# SCH_Arduino-Nano_2025-06-12.net
KiCad netlist of a schematic drawn in EasyEDA
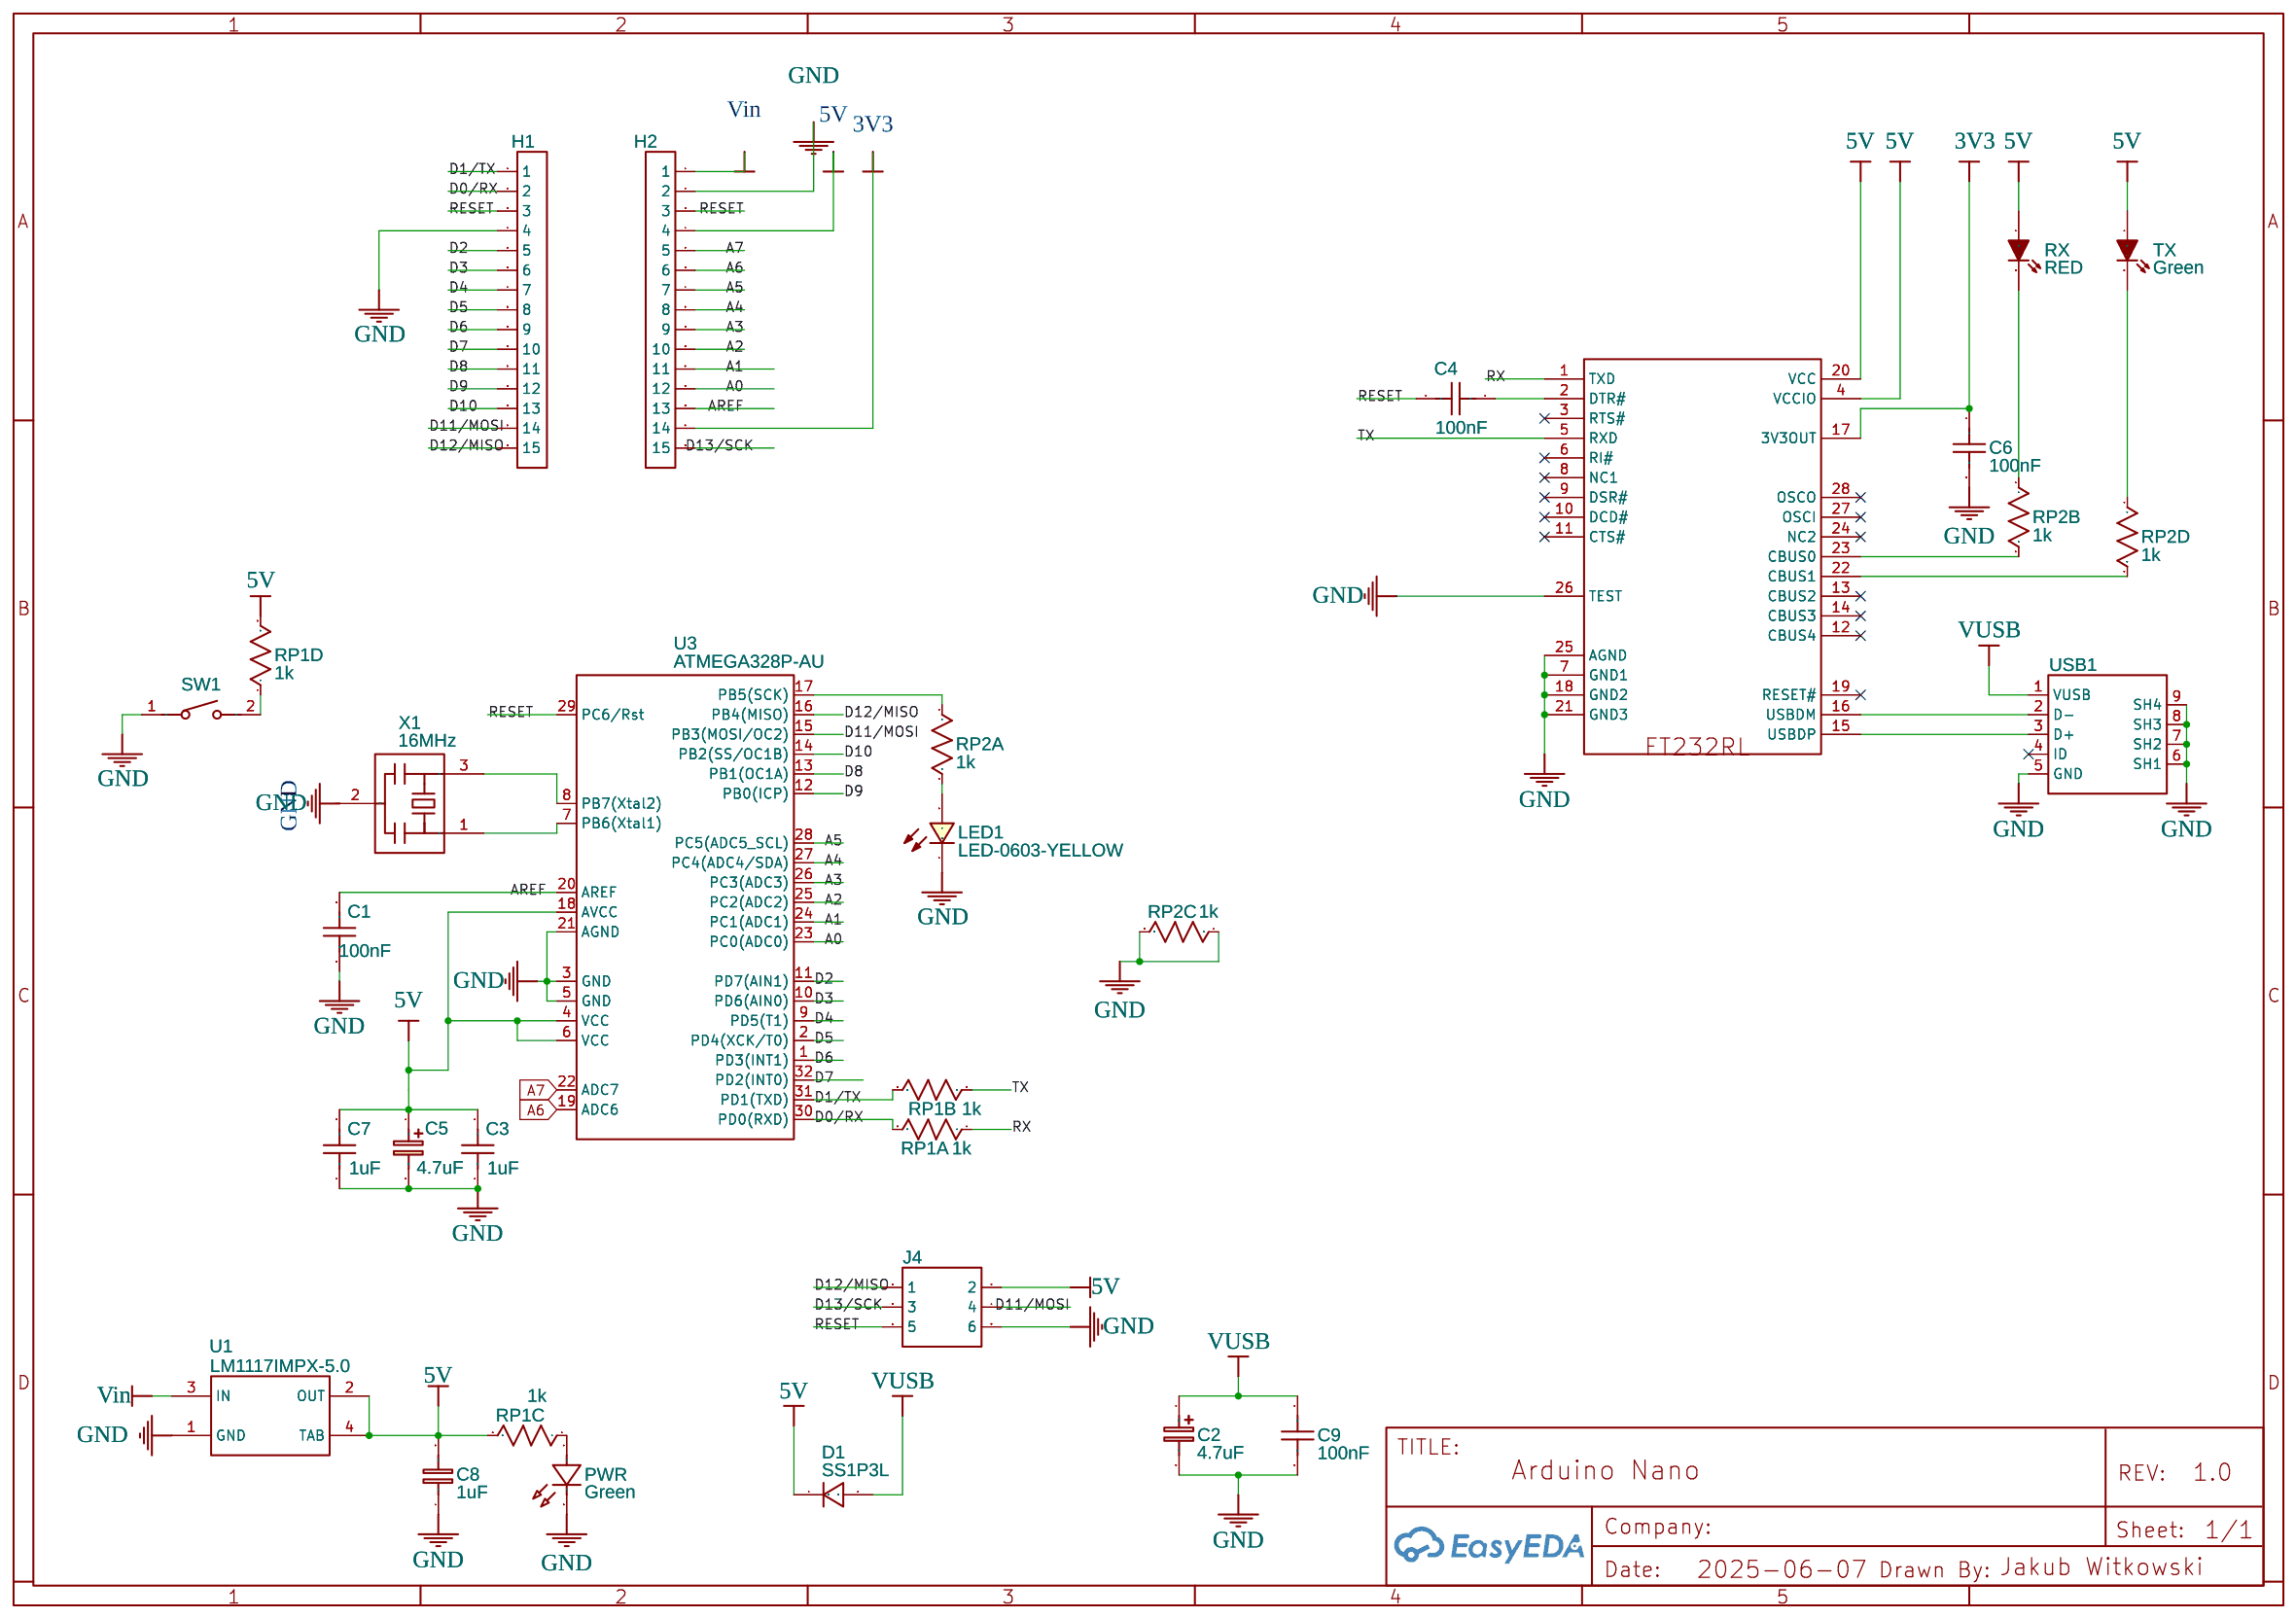
[diagram p0: schematic sheet]

(export (version "E")
  (design (tool "Eeschema 10.0.6"))
  (components
    (comp (ref "C1") (value "100nF") (libsource (lib "") (part "C_0603_US_1")))
    (comp (ref "C2") (value "4.7uF") (libsource (lib "") (part "C_Tan_SMD_A_EU_1")))
    (comp (ref "C3") (value "1uF") (libsource (lib "") (part "C_0603_US_1")))
    (comp (ref "C4") (value "100nF") (libsource (lib "") (part "C_0603_US")))
    (comp (ref "C5") (value "4.7uF") (libsource (lib "") (part "C_Tan_SMD_A_EU")))
    (comp (ref "C6") (value "100nF") (libsource (lib "") (part "C_0603_US_2")))
    (comp (ref "C7") (value "1uF") (libsource (lib "") (part "C_0603_US_1")))
    (comp (ref "C8") (value "1uF") (libsource (lib "") (part "C_0603_EU")))
    (comp (ref "C9") (value "100nF") (libsource (lib "") (part "C_0603_US_2")))
    (comp (ref "D1")
      (value "SS1P3L")
      (fields (field (name "Manufacturer Part") "1N4148W") (field (name "Manufacturer") "Tak Cheong"))
      (libsource (lib "") (part "1N4148W"))
    )
    (comp (ref "H1")
      (value "Header-Female-2.54_1x15")
      (fields
        (field (name "Manufacturer Part") "220S-1*15P H=8.5MM Ytype Gold-plated")
        (field (name "Manufacturer") "Ckmtw")
      )
      (libsource (lib "") (part "Header-Female-2.54_1x15_1"))
    )
    (comp (ref "H2")
      (value "Header-Female-2.54_1x15")
      (fields
        (field (name "Manufacturer Part") "220S-1*15P H=8.5MM Ytype Gold-plated")
        (field (name "Manufacturer") "Ckmtw")
      )
      (libsource (lib "") (part "Header-Female-2.54_1x15"))
    )
    (comp (ref "J4") (value "HDR-M-2.54_2x3") (libsource (lib "") (part "HDR-M-2.54_2x3")))
    (comp (ref "LED1")
      (value "LED-0603-YELLOW")
      (fields
        (field (name "Manufacturer Part") "19-213/Y2C-CQ1R1L/3T")
        (field (name "Manufacturer") "Everlight Elec")
      )
      (libsource (lib "") (part "LED-0603-YELLOW"))
    )
    (comp (ref "PWR")
      (value "Green")
      (fields (field (name "Manufacturer Part") "GreenLED"))
      (libsource (lib "") (part "GREENLED_C9900016840"))
    )
    (comp (ref "RP1A") (value "1k") (libsource (lib "") (part "R_0603_US_4")))
    (comp (ref "RP1B") (value "1k") (libsource (lib "") (part "R_0603_US_3")))
    (comp (ref "RP1C") (value "1k") (libsource (lib "") (part "R_0603_US_5")))
    (comp (ref "RP1D") (value "1k") (libsource (lib "") (part "R_0603_US")))
    (comp (ref "RP2A") (value "1k") (libsource (lib "") (part "R_0603_US_7")))
    (comp (ref "RP2B") (value "1k") (libsource (lib "") (part "R_0603_US_6")))
    (comp (ref "RP2C") (value "1k") (libsource (lib "") (part "R_0603_US_1")))
    (comp (ref "RP2D") (value "1k") (libsource (lib "") (part "R_0603_US_2")))
    (comp (ref "RX")
      (value "RED")
      (fields (field (name "Manufacturer Part") "KT-0603R") (field (name "Manufacturer") "Hubei KENTO Elec"))
      (libsource (lib "") (part "LED-0603-RED"))
    )
    (comp (ref "SW1")
      (value "TS-1088-AR02016")
      (fields (field (name "Manufacturer") "XUNPU"))
      (libsource (lib "") (part "TS-1088-AR02016"))
    )
    (comp (ref "TX")
      (value "Green")
      (fields
        (field (name "Manufacturer Part") "SZYY0603YG")
        (field (name "Manufacturer") "Yongyu Photoelectric")
      )
      (libsource (lib "") (part "LED-0603-GREEN"))
    )
    (comp (ref "U1")
      (value "LM1117IMPX-5.0")
      (fields (field (name "Manufacturer") "TI(德州仪器)"))
      (libsource (lib "") (part "LM1117IMPX-5.0"))
    )
    (comp (ref "U2")
      (value "FT232RL")
      (fields (field (name "Manufacturer Part") "?"))
      (libsource (lib "") (part "Unknown_795_-630"))
    )
    (comp (ref "U3")
      (value "ATMEGA328P-AU")
      (fields (field (name "Manufacturer") "Microchip Technology / Atmel"))
      (libsource (lib "") (part "ATMEGA328P-AU"))
    )
    (comp (ref "USB1") (value "USB_MINI") (libsource (lib "") (part "USB_MINI")))
    (comp (ref "X1")
      (value "16MHz")
      (fields (field (name "Manufacturer Part") "CSTCE16M0V53-R0") (field (name "Manufacturer") "MuRata"))
      (libsource (lib "") (part "CSTCE16M0V53C-R0"))
    )
  )
  (nets
    (net (code "1") (name "/A0") (class "Default")
      (node (ref "H2") (pin "12") (pinfunction "12_12") (pintype "unspecified"))
      (node (ref "U3") (pin "23") (pinfunction "PC0(ADC0)_23") (pintype "unspecified"))
    )
    (net (code "2") (name "/A1") (class "Default")
      (node (ref "H2") (pin "11") (pinfunction "11_11") (pintype "unspecified"))
      (node (ref "U3") (pin "24") (pinfunction "PC1(ADC1)_24") (pintype "unspecified"))
    )
    (net (code "3") (name "/A2") (class "Default")
      (node (ref "H2") (pin "10") (pinfunction "10_10") (pintype "unspecified"))
      (node (ref "U3") (pin "25") (pinfunction "PC2(ADC2)_25") (pintype "unspecified"))
    )
    (net (code "4") (name "/A3") (class "Default")
      (node (ref "H2") (pin "9") (pinfunction "9_9") (pintype "unspecified"))
      (node (ref "U3") (pin "26") (pinfunction "PC3(ADC3)_26") (pintype "unspecified"))
    )
    (net (code "5") (name "/A4") (class "Default")
      (node (ref "H2") (pin "8") (pinfunction "8_8") (pintype "unspecified"))
      (node (ref "U3") (pin "27") (pinfunction "PC4(ADC4/SDA)_27") (pintype "unspecified"))
    )
    (net (code "6") (name "/A5") (class "Default")
      (node (ref "H2") (pin "7") (pinfunction "7_7") (pintype "unspecified"))
      (node (ref "U3") (pin "28") (pinfunction "PC5(ADC5_SCL)_28") (pintype "unspecified"))
    )
    (net (code "7") (name "/AREF") (class "Default")
      (node (ref "C1") (pin "2") (pinfunction "2_2") (pintype "unspecified"))
      (node (ref "H2") (pin "13") (pinfunction "13_13") (pintype "unspecified"))
      (node (ref "U3") (pin "20") (pinfunction "AREF_20") (pintype "unspecified"))
    )
    (net (code "8") (name "/D0{slash}RX") (class "Default")
      (node (ref "H1") (pin "2") (pinfunction "2_2") (pintype "unspecified"))
      (node (ref "RP1A") (pin "2") (pinfunction "2_2") (pintype "unspecified"))
      (node (ref "U3") (pin "30") (pinfunction "PD0(RXD)_30") (pintype "unspecified"))
    )
    (net (code "9") (name "/D1{slash}TX") (class "Default")
      (node (ref "H1") (pin "1") (pinfunction "1_1") (pintype "unspecified"))
      (node (ref "RP1B") (pin "2") (pinfunction "2_2") (pintype "unspecified"))
      (node (ref "U3") (pin "31") (pinfunction "PD1(TXD)_31") (pintype "unspecified"))
    )
    (net (code "10") (name "/D2") (class "Default")
      (node (ref "H1") (pin "5") (pinfunction "5_5") (pintype "unspecified"))
      (node (ref "U3") (pin "11") (pinfunction "PD7(AIN1)_11") (pintype "unspecified"))
    )
    (net (code "11") (name "/D3") (class "Default")
      (node (ref "H1") (pin "6") (pinfunction "6_6") (pintype "unspecified"))
      (node (ref "U3") (pin "10") (pinfunction "PD6(AIN0)_10") (pintype "unspecified"))
    )
    (net (code "12") (name "/D4") (class "Default")
      (node (ref "H1") (pin "7") (pinfunction "7_7") (pintype "unspecified"))
      (node (ref "U3") (pin "9") (pinfunction "PD5(T1)_9") (pintype "unspecified"))
    )
    (net (code "13") (name "/D5") (class "Default")
      (node (ref "H1") (pin "8") (pinfunction "8_8") (pintype "unspecified"))
      (node (ref "U3") (pin "2") (pinfunction "PD4(XCK/T0)_2") (pintype "unspecified"))
    )
    (net (code "14") (name "/D6") (class "Default")
      (node (ref "H1") (pin "9") (pinfunction "9_9") (pintype "unspecified"))
      (node (ref "U3") (pin "1") (pinfunction "PD3(INT1)_1") (pintype "unspecified"))
    )
    (net (code "15") (name "/D7") (class "Default")
      (node (ref "H1") (pin "10") (pinfunction "10_10") (pintype "unspecified"))
      (node (ref "U3") (pin "32") (pinfunction "PD2(INT0)_32") (pintype "unspecified"))
    )
    (net (code "16") (name "/D8") (class "Default")
      (node (ref "H1") (pin "11") (pinfunction "11_11") (pintype "unspecified"))
      (node (ref "U3") (pin "13") (pinfunction "PB1(OC1A)_13") (pintype "unspecified"))
    )
    (net (code "17") (name "/D9") (class "Default")
      (node (ref "H1") (pin "12") (pinfunction "12_12") (pintype "unspecified"))
      (node (ref "U3") (pin "12") (pinfunction "PB0(ICP)_12") (pintype "unspecified"))
    )
    (net (code "18") (name "/D10") (class "Default")
      (node (ref "H1") (pin "13") (pinfunction "13_13") (pintype "unspecified"))
      (node (ref "U3") (pin "14") (pinfunction "PB2(SS/OC1B)_14") (pintype "unspecified"))
    )
    (net (code "19") (name "/D11{slash}MOSI") (class "Default")
      (node (ref "H1") (pin "14") (pinfunction "14_14") (pintype "unspecified"))
      (node (ref "J4") (pin "4") (pinfunction "4_4") (pintype "input"))
      (node (ref "U3") (pin "15") (pinfunction "PB3(MOSI/OC2)_15") (pintype "unspecified"))
    )
    (net (code "20") (name "/D12{slash}MISO") (class "Default")
      (node (ref "H1") (pin "15") (pinfunction "15_15") (pintype "unspecified"))
      (node (ref "J4") (pin "1") (pinfunction "1_1") (pintype "input"))
      (node (ref "U3") (pin "16") (pinfunction "PB4(MISO)_16") (pintype "unspecified"))
    )
    (net (code "21") (name "/D13{slash}SCK") (class "Default")
      (node (ref "H2") (pin "15") (pinfunction "15_15") (pintype "unspecified"))
      (node (ref "J4") (pin "3") (pinfunction "3_3") (pintype "input"))
    )
    (net (code "22") (name "/RESET") (class "Default")
      (node (ref "C4") (pin "2") (pinfunction "2_2") (pintype "unspecified"))
      (node (ref "H1") (pin "3") (pinfunction "3_3") (pintype "unspecified"))
      (node (ref "H2") (pin "3") (pinfunction "3_3") (pintype "unspecified"))
      (node (ref "J4") (pin "5") (pinfunction "5_5") (pintype "input"))
      (node (ref "U3") (pin "29") (pinfunction "PC6/Rst_29") (pintype "unspecified"))
    )
    (net (code "23") (name "/RX") (class "Default")
      (node (ref "RP1A") (pin "1") (pinfunction "1_1") (pintype "unspecified"))
      (node (ref "U2") (pin "1") (pinfunction "TXD_1") (pintype "unspecified"))
    )
    (net (code "24") (name "/TX") (class "Default")
      (node (ref "RP1B") (pin "1") (pinfunction "1_1") (pintype "unspecified"))
      (node (ref "U2") (pin "5") (pinfunction "RXD_5") (pintype "unspecified"))
    )
    (net (code "25") (name "3V3") (class "Default")
      (node (ref "C6") (pin "1") (pinfunction "1_1") (pintype "unspecified"))
      (node (ref "H2") (pin "14") (pinfunction "14_14") (pintype "unspecified"))
      (node (ref "U2") (pin "17") (pinfunction "3V3OUT_17") (pintype "unspecified"))
    )
    (net (code "26") (name "5V") (class "Default")
      (node (ref "C3") (pin "2") (pinfunction "2_2") (pintype "unspecified"))
      (node (ref "C5") (pin "1") (pinfunction "1_1") (pintype "unspecified"))
      (node (ref "C7") (pin "2") (pinfunction "2_2") (pintype "unspecified"))
      (node (ref "C8") (pin "2") (pinfunction "2_2") (pintype "unspecified"))
      (node (ref "D1") (pin "1") (pinfunction "1_1") (pintype "unspecified"))
      (node (ref "H2") (pin "4") (pinfunction "4_4") (pintype "unspecified"))
      (node (ref "J4") (pin "2") (pinfunction "2_2") (pintype "input"))
      (node (ref "RP1C") (pin "2") (pinfunction "2_2") (pintype "unspecified"))
      (node (ref "RP1D") (pin "2") (pinfunction "2_2") (pintype "unspecified"))
      (node (ref "RX") (pin "1") (pinfunction "1_1") (pintype "unspecified"))
      (node (ref "TX") (pin "1") (pinfunction "1_1") (pintype "unspecified"))
      (node (ref "U1") (pin "2") (pinfunction "OUT_2") (pintype "passive"))
      (node (ref "U1") (pin "4") (pinfunction "TAB_4") (pintype "passive"))
      (node (ref "U2") (pin "20") (pinfunction "VCC_20") (pintype "unspecified"))
      (node (ref "U2") (pin "4") (pinfunction "VCCIO_4") (pintype "unspecified"))
      (node (ref "U3") (pin "18") (pinfunction "AVCC_18") (pintype "unspecified"))
      (node (ref "U3") (pin "4") (pinfunction "VCC_4") (pintype "unspecified"))
      (node (ref "U3") (pin "6") (pinfunction "VCC_6") (pintype "unspecified"))
    )
    (net (code "27") (name "A6") (class "Default")
      (node (ref "H2") (pin "6") (pinfunction "6_6") (pintype "unspecified"))
      (node (ref "U3") (pin "19") (pinfunction "ADC6_19") (pintype "unspecified"))
    )
    (net (code "28") (name "A7") (class "Default")
      (node (ref "H2") (pin "5") (pinfunction "5_5") (pintype "unspecified"))
      (node (ref "U3") (pin "22") (pinfunction "ADC7_22") (pintype "unspecified"))
    )
    (net (code "29") (name "GND") (class "Default")
      (node (ref "C1") (pin "1") (pinfunction "1_1") (pintype "unspecified"))
      (node (ref "C2") (pin "2") (pinfunction "2_2") (pintype "unspecified"))
      (node (ref "C3") (pin "1") (pinfunction "1_1") (pintype "unspecified"))
      (node (ref "C5") (pin "2") (pinfunction "2_2") (pintype "unspecified"))
      (node (ref "C6") (pin "2") (pinfunction "2_2") (pintype "unspecified"))
      (node (ref "C7") (pin "1") (pinfunction "1_1") (pintype "unspecified"))
      (node (ref "C8") (pin "1") (pinfunction "1_1") (pintype "unspecified"))
      (node (ref "C9") (pin "2") (pinfunction "2_2") (pintype "unspecified"))
      (node (ref "H1") (pin "4") (pinfunction "4_4") (pintype "unspecified"))
      (node (ref "H2") (pin "2") (pinfunction "2_2") (pintype "unspecified"))
      (node (ref "J4") (pin "6") (pinfunction "6_6") (pintype "input"))
      (node (ref "LED1") (pin "1") (pinfunction "C_1") (pintype "input"))
      (node (ref "PWR") (pin "2") (pinfunction "A_2") (pintype "unspecified"))
      (node (ref "RP2C") (pin "1") (pinfunction "1_1") (pintype "unspecified"))
      (node (ref "RP2C") (pin "2") (pinfunction "2_2") (pintype "unspecified"))
      (node (ref "SW1") (pin "1") (pinfunction "1_1") (pintype "unspecified"))
      (node (ref "U1") (pin "1") (pinfunction "GND_1") (pintype "passive"))
      (node (ref "U2") (pin "18") (pinfunction "GND2_18") (pintype "unspecified"))
      (node (ref "U2") (pin "21") (pinfunction "GND3_21") (pintype "unspecified"))
      (node (ref "U2") (pin "25") (pinfunction "AGND_25") (pintype "unspecified"))
      (node (ref "U2") (pin "26") (pinfunction "TEST_26") (pintype "unspecified"))
      (node (ref "U2") (pin "7") (pinfunction "GND1_7") (pintype "unspecified"))
      (node (ref "U3") (pin "21") (pinfunction "AGND_21") (pintype "unspecified"))
      (node (ref "U3") (pin "3") (pinfunction "GND_3") (pintype "unspecified"))
      (node (ref "U3") (pin "5") (pinfunction "GND_5") (pintype "unspecified"))
      (node (ref "USB1") (pin "5") (pinfunction "GND_5") (pintype "unspecified"))
      (node (ref "USB1") (pin "6") (pinfunction "SH1_6") (pintype "unspecified"))
      (node (ref "USB1") (pin "7") (pinfunction "SH2_7") (pintype "unspecified"))
      (node (ref "USB1") (pin "8") (pinfunction "SH3_8") (pintype "unspecified"))
      (node (ref "USB1") (pin "9") (pinfunction "SH4_9") (pintype "unspecified"))
      (node (ref "X1") (pin "2") (pinfunction "2_2") (pintype "unspecified"))
    )
    (net (code "30") (name "Net-(LED1-A)") (class "Default")
      (node (ref "LED1") (pin "2") (pinfunction "A_2") (pintype "input"))
      (node (ref "RP2A") (pin "2") (pinfunction "2_2") (pintype "unspecified"))
    )
    (net (code "31") (name "Net-(PWR-K)") (class "Default")
      (node (ref "PWR") (pin "1") (pinfunction "K_1") (pintype "unspecified"))
      (node (ref "RP1C") (pin "1") (pinfunction "1_1") (pintype "unspecified"))
    )
    (net (code "32") (name "Net-(RP1D-Pad1)") (class "Default")
      (node (ref "RP1D") (pin "1") (pinfunction "1_1") (pintype "unspecified"))
      (node (ref "SW1") (pin "2") (pinfunction "2_2") (pintype "unspecified"))
    )
    (net (code "33") (name "Net-(RP2B-Pad1)") (class "Default")
      (node (ref "RP2B") (pin "1") (pinfunction "1_1") (pintype "unspecified"))
      (node (ref "RX") (pin "2") (pinfunction "2_2") (pintype "unspecified"))
    )
    (net (code "34") (name "Net-(RP2D-Pad1)") (class "Default")
      (node (ref "RP2D") (pin "1") (pinfunction "1_1") (pintype "unspecified"))
      (node (ref "TX") (pin "2") (pinfunction "2_2") (pintype "unspecified"))
    )
    (net (code "35") (name "Net-(U2-CBUS0)") (class "Default")
      (node (ref "RP2B") (pin "2") (pinfunction "2_2") (pintype "unspecified"))
      (node (ref "U2") (pin "23") (pinfunction "CBUS0_23") (pintype "unspecified"))
    )
    (net (code "36") (name "Net-(U2-CBUS1)") (class "Default")
      (node (ref "RP2D") (pin "2") (pinfunction "2_2") (pintype "unspecified"))
      (node (ref "U2") (pin "22") (pinfunction "CBUS1_22") (pintype "unspecified"))
    )
    (net (code "37") (name "Net-(U2-DTR#)") (class "Default")
      (node (ref "C4") (pin "1") (pinfunction "1_1") (pintype "unspecified"))
      (node (ref "U2") (pin "2") (pinfunction "DTR#_2") (pintype "unspecified"))
    )
    (net (code "38") (name "Net-(U2-USBDM)") (class "Default")
      (node (ref "U2") (pin "16") (pinfunction "USBDM_16") (pintype "unspecified"))
      (node (ref "USB1") (pin "2") (pinfunction "D-_2") (pintype "unspecified"))
    )
    (net (code "39") (name "Net-(U2-USBDP)") (class "Default")
      (node (ref "U2") (pin "15") (pinfunction "USBDP_15") (pintype "unspecified"))
      (node (ref "USB1") (pin "3") (pinfunction "D+_3") (pintype "unspecified"))
    )
    (net (code "40") (name "Net-(U3-PB5(SCK))") (class "Default")
      (node (ref "RP2A") (pin "1") (pinfunction "1_1") (pintype "unspecified"))
      (node (ref "U3") (pin "17") (pinfunction "PB5(SCK)_17") (pintype "unspecified"))
    )
    (net (code "41") (name "Net-(U3-PB6(Xtal1))") (class "Default")
      (node (ref "U3") (pin "7") (pinfunction "PB6(Xtal1)_7") (pintype "unspecified"))
      (node (ref "X1") (pin "1") (pinfunction "1_1") (pintype "unspecified"))
    )
    (net (code "42") (name "Net-(U3-PB7(Xtal2))") (class "Default")
      (node (ref "U3") (pin "8") (pinfunction "PB7(Xtal2)_8") (pintype "unspecified"))
      (node (ref "X1") (pin "3") (pinfunction "3_3") (pintype "unspecified"))
    )
    (net (code "43") (name "VUSB") (class "Default")
      (node (ref "C2") (pin "1") (pinfunction "1_1") (pintype "unspecified"))
      (node (ref "C9") (pin "1") (pinfunction "1_1") (pintype "unspecified"))
      (node (ref "D1") (pin "2") (pinfunction "2_2") (pintype "unspecified"))
      (node (ref "USB1") (pin "1") (pinfunction "VUSB_1") (pintype "unspecified"))
    )
    (net (code "44") (name "Vin") (class "Default")
      (node (ref "H2") (pin "1") (pinfunction "1_1") (pintype "unspecified"))
      (node (ref "U1") (pin "3") (pinfunction "IN_3") (pintype "passive"))
    )
    (net (code "45") (name "unconnected-(U2-CBUS2-Pad13)") (class "Default")
      (node (ref "U2") (pin "13") (pinfunction "CBUS2_13") (pintype "unspecified+no_connect"))
    )
    (net (code "46") (name "unconnected-(U2-CBUS3-Pad14)") (class "Default")
      (node (ref "U2") (pin "14") (pinfunction "CBUS3_14") (pintype "unspecified+no_connect"))
    )
    (net (code "47") (name "unconnected-(U2-CBUS4-Pad12)") (class "Default")
      (node (ref "U2") (pin "12") (pinfunction "CBUS4_12") (pintype "unspecified+no_connect"))
    )
    (net (code "48") (name "unconnected-(U2-CTS#-Pad11)") (class "Default")
      (node (ref "U2") (pin "11") (pinfunction "CTS#_11") (pintype "unspecified+no_connect"))
    )
    (net (code "49") (name "unconnected-(U2-DCD#-Pad10)") (class "Default")
      (node (ref "U2") (pin "10") (pinfunction "DCD#_10") (pintype "unspecified+no_connect"))
    )
    (net (code "50") (name "unconnected-(U2-DSR#-Pad9)") (class "Default")
      (node (ref "U2") (pin "9") (pinfunction "DSR#_9") (pintype "unspecified+no_connect"))
    )
    (net (code "51") (name "unconnected-(U2-NC1-Pad8)") (class "Default")
      (node (ref "U2") (pin "8") (pinfunction "NC1_8") (pintype "unspecified+no_connect"))
    )
    (net (code "52") (name "unconnected-(U2-NC2-Pad24)") (class "Default")
      (node (ref "U2") (pin "24") (pinfunction "NC2_24") (pintype "unspecified+no_connect"))
    )
    (net (code "53") (name "unconnected-(U2-OSCI-Pad27)") (class "Default")
      (node (ref "U2") (pin "27") (pinfunction "OSCI_27") (pintype "unspecified+no_connect"))
    )
    (net (code "54") (name "unconnected-(U2-OSCO-Pad28)") (class "Default")
      (node (ref "U2") (pin "28") (pinfunction "OSCO_28") (pintype "unspecified+no_connect"))
    )
    (net (code "55") (name "unconnected-(U2-RESET#-Pad19)") (class "Default")
      (node (ref "U2") (pin "19") (pinfunction "RESET#_19") (pintype "unspecified+no_connect"))
    )
    (net (code "56") (name "unconnected-(U2-RI#-Pad6)") (class "Default")
      (node (ref "U2") (pin "6") (pinfunction "RI#_6") (pintype "unspecified+no_connect"))
    )
    (net (code "57") (name "unconnected-(U2-RTS#-Pad3)") (class "Default")
      (node (ref "U2") (pin "3") (pinfunction "RTS#_3") (pintype "unspecified+no_connect"))
    )
    (net (code "58") (name "unconnected-(USB1-ID-Pad4)") (class "Default")
      (node (ref "USB1") (pin "4") (pinfunction "ID_4") (pintype "unspecified+no_connect"))
    )
  )
)
